# TriggerPadSchematic.net
KiCad netlist of a schematic drawn in Altium Designer
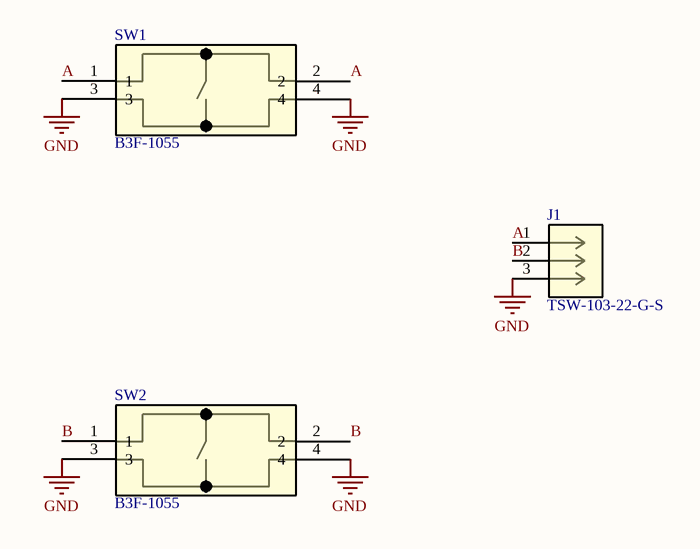
[diagram p0: TriggerPadSchematic.SchDoc]

(export (version "E")
  (design (tool "Eeschema 10.0.6"))
  (components
    (comp (ref "J1")
      (value "TSW-103-22-G-S")
      (footprint "CON3_1X3_TU_TSW")
      (description "No Description Available")
      (fields (field (name "COPYRIGHT") "Copyright (C) 2026 Ultra Librarian. All rights reserved."))
      (libsource (lib "TSW-103-22-G-S") (part "TSW-103-22-G-S"))
    )
    (comp (ref "SW1")
      (value "B3F-1055")
      (footprint "SW_B3F-1050_OMR")
      (description "Description")
      (fields (field (name "COPYRIGHT") "Copyright (C) 2025 Ultra Librarian. All rights reserved."))
      (libsource (lib "B3F-1055") (part "B3F-1055"))
    )
    (comp (ref "SW2")
      (value "B3F-1055")
      (footprint "SW_B3F-1050_OMR")
      (description "Description")
      (fields (field (name "COPYRIGHT") "Copyright (C) 2025 Ultra Librarian. All rights reserved."))
      (libsource (lib "B3F-1055") (part "B3F-1055"))
    )
  )
  (nets
    (net (code "1") (name "/A") (class "Default")
      (node (ref "J1") (pin "1") (pinfunction "1_1") (pintype "passive"))
      (node (ref "SW1") (pin "1") (pinfunction "1_1") (pintype "passive"))
      (node (ref "SW1") (pin "2") (pinfunction "2_2") (pintype "passive"))
    )
    (net (code "2") (name "/B") (class "Default")
      (node (ref "J1") (pin "2") (pinfunction "2_2") (pintype "passive"))
      (node (ref "SW2") (pin "1") (pinfunction "1_1") (pintype "passive"))
      (node (ref "SW2") (pin "2") (pinfunction "2_2") (pintype "passive"))
    )
    (net (code "3") (name "GND") (class "Default")
      (node (ref "J1") (pin "3") (pinfunction "3_3") (pintype "passive"))
      (node (ref "SW1") (pin "3") (pinfunction "3_3") (pintype "passive"))
      (node (ref "SW1") (pin "4") (pinfunction "4_4") (pintype "passive"))
      (node (ref "SW2") (pin "3") (pinfunction "3_3") (pintype "passive"))
      (node (ref "SW2") (pin "4") (pinfunction "4_4") (pintype "passive"))
    )
  )
)
